# SCHEM_1.net
KiCad netlist of a schematic drawn in Altium Designer
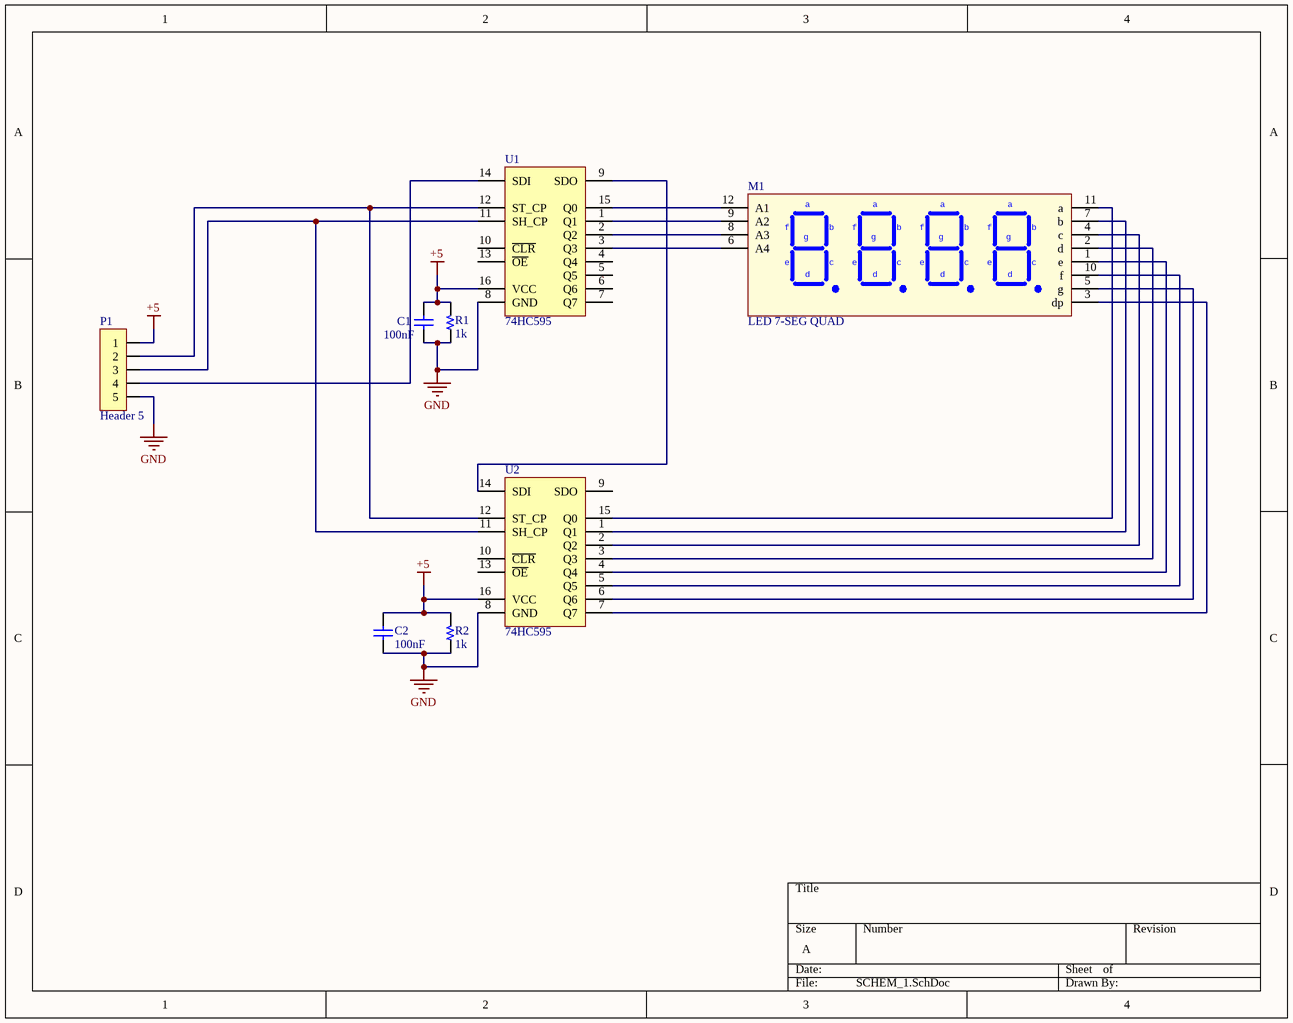
[diagram p0: SCHEM_1.SchDoc]

(export (version "E")
  (design (tool "Eeschema 10.0.6"))
  (components
    (comp (ref "C1")
      (value "100nF")
      (footprint "C 1210")
      (description "Capacitor non-pol")
      (libsource (lib "chipfc_libs") (part "Capacitor NP"))
    )
    (comp (ref "C2")
      (value "100nF")
      (footprint "C 1210")
      (description "Capacitor non-pol")
      (libsource (lib "chipfc_libs") (part "Capacitor NP"))
    )
    (comp (ref "M1")
      (value "LED 7-SEG QUAD")
      (footprint "LED/7SEG/0.56/QUAD")
      (description "LED 7-SEG 0.56 QUAD RED")
      (libsource (lib "led") (part "LED 7-SEG QUAD"))
    )
    (comp (ref "P1")
      (value "Header 5")
      (footprint "HDR/Header/5")
      (description "Header, 5-Pin")
      (libsource (lib "connectors") (part "Header 5"))
    )
    (comp (ref "R1")
      (value "1k")
      (footprint "R 1210")
      (description "Resistor")
      (libsource (lib "chipfc_libs") (part "Resistor"))
    )
    (comp (ref "R2")
      (value "1k")
      (footprint "R 1210")
      (description "Resistor")
      (libsource (lib "chipfc_libs") (part "Resistor"))
    )
    (comp (ref "U1")
      (value "74HC595")
      (footprint "SOIC-16")
      (description "8-bit serial-in, serial or parallel-out  shift register with output latches;  3-state")
      (libsource (lib "chipfc_libs") (part "74HC595"))
    )
    (comp (ref "U2")
      (value "74HC595")
      (footprint "SOIC-16")
      (description "8-bit serial-in, serial or parallel-out  shift register with output latches;  3-state")
      (libsource (lib "chipfc_libs") (part "74HC595"))
    )
  )
  (nets
    (net (code "1") (name "+5") (class "Default")
      (node (ref "C1") (pin "1") (pinfunction "1_1") (pintype "passive"))
      (node (ref "C2") (pin "1") (pinfunction "1_1") (pintype "passive"))
      (node (ref "P1") (pin "1") (pinfunction "1_1") (pintype "passive"))
      (node (ref "R1") (pin "2") (pinfunction "2_2") (pintype "passive"))
      (node (ref "R2") (pin "2") (pinfunction "2_2") (pintype "passive"))
      (node (ref "U1") (pin "16") (pinfunction "VCC_16") (pintype "passive"))
      (node (ref "U2") (pin "16") (pinfunction "VCC_16") (pintype "passive"))
    )
    (net (code "2") (name "GND") (class "Default")
      (node (ref "C1") (pin "2") (pinfunction "2_2") (pintype "passive"))
      (node (ref "C2") (pin "2") (pinfunction "2_2") (pintype "passive"))
      (node (ref "P1") (pin "5") (pinfunction "5_5") (pintype "passive"))
      (node (ref "R1") (pin "1") (pinfunction "1_1") (pintype "passive"))
      (node (ref "R2") (pin "1") (pinfunction "1_1") (pintype "passive"))
      (node (ref "U1") (pin "8") (pinfunction "GND_8") (pintype "passive"))
      (node (ref "U2") (pin "8") (pinfunction "GND_8") (pintype "passive"))
    )
    (net (code "3") (name "Net-(M1-A1)") (class "Default")
      (node (ref "M1") (pin "12") (pinfunction "A1_12") (pintype "passive"))
      (node (ref "U1") (pin "15") (pinfunction "Q0_15") (pintype "passive"))
    )
    (net (code "4") (name "Net-(M1-A2)") (class "Default")
      (node (ref "M1") (pin "9") (pinfunction "A2_9") (pintype "passive"))
      (node (ref "U1") (pin "1") (pinfunction "Q1_1") (pintype "passive"))
    )
    (net (code "5") (name "Net-(M1-A3)") (class "Default")
      (node (ref "M1") (pin "8") (pinfunction "A3_8") (pintype "passive"))
      (node (ref "U1") (pin "2") (pinfunction "Q2_2") (pintype "passive"))
    )
    (net (code "6") (name "Net-(M1-A4)") (class "Default")
      (node (ref "M1") (pin "6") (pinfunction "A4_6") (pintype "passive"))
      (node (ref "U1") (pin "3") (pinfunction "Q3_3") (pintype "passive"))
    )
    (net (code "7") (name "Net-(M1-a)") (class "Default")
      (node (ref "M1") (pin "11") (pinfunction "a_11") (pintype "passive"))
      (node (ref "U2") (pin "15") (pinfunction "Q0_15") (pintype "passive"))
    )
    (net (code "8") (name "Net-(M1-b)") (class "Default")
      (node (ref "M1") (pin "7") (pinfunction "b_7") (pintype "passive"))
      (node (ref "U2") (pin "1") (pinfunction "Q1_1") (pintype "passive"))
    )
    (net (code "9") (name "Net-(M1-c)") (class "Default")
      (node (ref "M1") (pin "4") (pinfunction "c_4") (pintype "passive"))
      (node (ref "U2") (pin "2") (pinfunction "Q2_2") (pintype "passive"))
    )
    (net (code "10") (name "Net-(M1-d)") (class "Default")
      (node (ref "M1") (pin "2") (pinfunction "d_2") (pintype "passive"))
      (node (ref "U2") (pin "3") (pinfunction "Q3_3") (pintype "passive"))
    )
    (net (code "11") (name "Net-(M1-dp)") (class "Default")
      (node (ref "M1") (pin "3") (pinfunction "dp_3") (pintype "passive"))
      (node (ref "U2") (pin "7") (pinfunction "Q7_7") (pintype "passive"))
    )
    (net (code "12") (name "Net-(M1-e)") (class "Default")
      (node (ref "M1") (pin "1") (pinfunction "e_1") (pintype "passive"))
      (node (ref "U2") (pin "4") (pinfunction "Q4_4") (pintype "passive"))
    )
    (net (code "13") (name "Net-(M1-f)") (class "Default")
      (node (ref "M1") (pin "10") (pinfunction "f_10") (pintype "passive"))
      (node (ref "U2") (pin "5") (pinfunction "Q5_5") (pintype "passive"))
    )
    (net (code "14") (name "Net-(M1-g)") (class "Default")
      (node (ref "M1") (pin "5") (pinfunction "g_5") (pintype "passive"))
      (node (ref "U2") (pin "6") (pinfunction "Q6_6") (pintype "passive"))
    )
    (net (code "15") (name "Net-(U1-SDI)") (class "Default")
      (node (ref "P1") (pin "4") (pinfunction "4_4") (pintype "passive"))
      (node (ref "U1") (pin "14") (pinfunction "SDI_14") (pintype "passive"))
    )
    (net (code "16") (name "Net-(U1-SDO)") (class "Default")
      (node (ref "U1") (pin "9") (pinfunction "SDO_9") (pintype "passive"))
      (node (ref "U2") (pin "14") (pinfunction "SDI_14") (pintype "passive"))
    )
    (net (code "17") (name "Net-(U1-SH_CP)") (class "Default")
      (node (ref "P1") (pin "3") (pinfunction "3_3") (pintype "passive"))
      (node (ref "U1") (pin "11") (pinfunction "SH_CP_11") (pintype "passive"))
      (node (ref "U2") (pin "11") (pinfunction "SH_CP_11") (pintype "passive"))
    )
    (net (code "18") (name "Net-(U1-ST_CP)") (class "Default")
      (node (ref "P1") (pin "2") (pinfunction "2_2") (pintype "passive"))
      (node (ref "U1") (pin "12") (pinfunction "ST_CP_12") (pintype "passive"))
      (node (ref "U2") (pin "12") (pinfunction "ST_CP_12") (pintype "passive"))
    )
    (net (code "19") (name "unconnected-(U1-Q4-Pad4)") (class "Default")
      (node (ref "U1") (pin "4") (pinfunction "Q4_4") (pintype "passive"))
    )
    (net (code "20") (name "unconnected-(U1-Q5-Pad5)") (class "Default")
      (node (ref "U1") (pin "5") (pinfunction "Q5_5") (pintype "passive"))
    )
    (net (code "21") (name "unconnected-(U1-Q6-Pad6)") (class "Default")
      (node (ref "U1") (pin "6") (pinfunction "Q6_6") (pintype "passive"))
    )
    (net (code "22") (name "unconnected-(U1-Q7-Pad7)") (class "Default")
      (node (ref "U1") (pin "7") (pinfunction "Q7_7") (pintype "passive"))
    )
    (net (code "23") (name "unconnected-(U1-~{CLR}-Pad10)") (class "Default")
      (node (ref "U1") (pin "10") (pinfunction "~{CLR}_10") (pintype "passive"))
    )
    (net (code "24") (name "unconnected-(U1-~{OE}-Pad13)") (class "Default")
      (node (ref "U1") (pin "13") (pinfunction "~{OE}_13") (pintype "passive"))
    )
    (net (code "25") (name "unconnected-(U2-SDO-Pad9)") (class "Default")
      (node (ref "U2") (pin "9") (pinfunction "SDO_9") (pintype "passive"))
    )
    (net (code "26") (name "unconnected-(U2-~{CLR}-Pad10)") (class "Default")
      (node (ref "U2") (pin "10") (pinfunction "~{CLR}_10") (pintype "passive"))
    )
    (net (code "27") (name "unconnected-(U2-~{OE}-Pad13)") (class "Default")
      (node (ref "U2") (pin "13") (pinfunction "~{OE}_13") (pintype "passive"))
    )
  )
)
